# MCU.net
KiCad netlist of a schematic drawn in Altium Designer
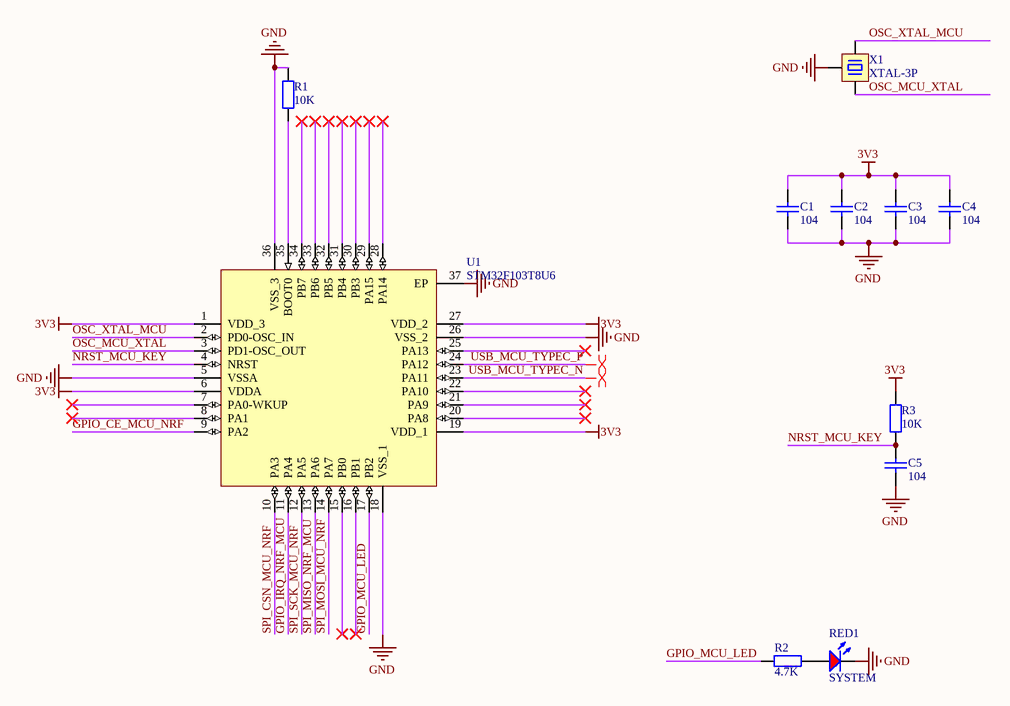
[diagram p0: MCU.SchDoc]

(export (version "E")
  (design (tool "Eeschema 10.0.6"))
  (components
    (comp (ref "C1")
      (value "104")
      (footprint "Cap-0402-M")
      (description "贴片陶瓷电容")
      (libsource (lib "Miscellaneous Base") (part "CAP"))
    )
    (comp (ref "C2")
      (value "104")
      (footprint "Cap-0402-M")
      (description "贴片陶瓷电容")
      (libsource (lib "Miscellaneous Base") (part "CAP"))
    )
    (comp (ref "C3")
      (value "104")
      (footprint "Cap-0402-M")
      (description "贴片陶瓷电容")
      (libsource (lib "Miscellaneous Base") (part "CAP"))
    )
    (comp (ref "C4")
      (value "104")
      (footprint "Cap-0402-M")
      (description "贴片陶瓷电容")
      (libsource (lib "Miscellaneous Base") (part "CAP"))
    )
    (comp (ref "C5")
      (value "104")
      (footprint "Cap-0402-M")
      (description "贴片陶瓷电容")
      (libsource (lib "Miscellaneous Base") (part "CAP"))
    )
    (comp (ref "R1")
      (value "10K")
      (footprint "Res-0402-M")
      (description "贴片电阻")
      (libsource (lib "Miscellaneous Base") (part "RES"))
    )
    (comp (ref "R2")
      (value "4.7K")
      (footprint "Res-0402-M")
      (description "贴片电阻")
      (libsource (lib "") (part "RES_1"))
    )
    (comp (ref "R3")
      (value "10K")
      (footprint "Res-0402-M")
      (description "贴片电阻")
      (libsource (lib "Miscellaneous Base") (part "RES"))
    )
    (comp (ref "RED1")
      (value "SYSTEM")
      (footprint "LED_0603_R")
      (description "发光二极管")
      (libsource (lib "Miscellaneous Transistor") (part "LED_SMD_RED"))
    )
    (comp (ref "U1")
      (value "STM32F103T8U6")
      (footprint "STM-VFQFPN36_L _2")
      (libsource (lib "Miscellaneous MCU") (part "STM32F103T8U6"))
    )
    (comp (ref "X1")
      (value "XTAL-3P")
      (footprint "OSC 3213-3P")
      (description "3脚无源晶振带电容")
      (libsource (lib "Miscellaneous XTAL") (part "XTAL-3P"))
    )
  )
  (nets
    (net (code "1") (name "/GPIO_CE_MCU_NRF") (class "Default")
      (node (ref "U1") (pin "9") (pinfunction "PA2_9") (pintype "bidirectional"))
    )
    (net (code "2") (name "/GPIO_IRQ_NRF_MCU") (class "Default")
      (node (ref "U1") (pin "11") (pinfunction "PA4_11") (pintype "bidirectional"))
    )
    (net (code "3") (name "/GPIO_MCU_LED") (class "Default")
      (node (ref "R2") (pin "2") (pinfunction "2_2") (pintype "passive"))
      (node (ref "U1") (pin "17") (pinfunction "PB2_17") (pintype "bidirectional"))
    )
    (net (code "4") (name "/NRST_MCU_KEY") (class "Default")
      (node (ref "C5") (pin "2") (pinfunction "2_2") (pintype "passive"))
      (node (ref "R3") (pin "1") (pinfunction "1_1") (pintype "passive"))
      (node (ref "U1") (pin "4") (pinfunction "NRST_4") (pintype "bidirectional"))
    )
    (net (code "5") (name "/OSC_MCU_XTAL") (class "Default")
      (node (ref "U1") (pin "3") (pinfunction "PD1-OSC_OUT_3") (pintype "bidirectional"))
      (node (ref "X1") (pin "3") (pinfunction "3_3") (pintype "passive"))
    )
    (net (code "6") (name "/OSC_XTAL_MCU") (class "Default")
      (node (ref "U1") (pin "2") (pinfunction "PD0-OSC_IN_2") (pintype "bidirectional"))
      (node (ref "X1") (pin "1") (pinfunction "1_1") (pintype "passive"))
    )
    (net (code "7") (name "/SPI_CSN_MCU_NRF") (class "Default")
      (node (ref "U1") (pin "10") (pinfunction "PA3_10") (pintype "bidirectional"))
    )
    (net (code "8") (name "/SPI_MISO_NRF_MCU") (class "Default")
      (node (ref "U1") (pin "13") (pinfunction "PA6_13") (pintype "bidirectional"))
    )
    (net (code "9") (name "/SPI_MOSI_MCU_NRF") (class "Default")
      (node (ref "U1") (pin "14") (pinfunction "PA7_14") (pintype "bidirectional"))
    )
    (net (code "10") (name "/SPI_SCK_MCU_NRF") (class "Default")
      (node (ref "U1") (pin "12") (pinfunction "PA5_12") (pintype "bidirectional"))
    )
    (net (code "11") (name "/USB_MCU_TYPEC_N") (class "Default")
      (node (ref "U1") (pin "23") (pinfunction "PA11_23") (pintype "bidirectional"))
    )
    (net (code "12") (name "/USB_MCU_TYPEC_P") (class "Default")
      (node (ref "U1") (pin "24") (pinfunction "PA12_24") (pintype "bidirectional"))
    )
    (net (code "13") (name "3V3") (class "Default")
      (node (ref "C1") (pin "2") (pinfunction "2_2") (pintype "passive"))
      (node (ref "C2") (pin "2") (pinfunction "2_2") (pintype "passive"))
      (node (ref "C3") (pin "2") (pinfunction "2_2") (pintype "passive"))
      (node (ref "C4") (pin "2") (pinfunction "2_2") (pintype "passive"))
      (node (ref "R3") (pin "2") (pinfunction "2_2") (pintype "passive"))
      (node (ref "U1") (pin "1") (pinfunction "VDD_3_1") (pintype "power_in"))
      (node (ref "U1") (pin "19") (pinfunction "VDD_1_19") (pintype "power_in"))
      (node (ref "U1") (pin "27") (pinfunction "VDD_2_27") (pintype "power_in"))
      (node (ref "U1") (pin "6") (pinfunction "VDDA_6") (pintype "power_in"))
    )
    (net (code "14") (name "GND") (class "Default")
      (node (ref "C1") (pin "1") (pinfunction "1_1") (pintype "passive"))
      (node (ref "C2") (pin "1") (pinfunction "1_1") (pintype "passive"))
      (node (ref "C3") (pin "1") (pinfunction "1_1") (pintype "passive"))
      (node (ref "C4") (pin "1") (pinfunction "1_1") (pintype "passive"))
      (node (ref "C5") (pin "1") (pinfunction "1_1") (pintype "passive"))
      (node (ref "R1") (pin "2") (pinfunction "2_2") (pintype "passive"))
      (node (ref "RED1") (pin "2") (pinfunction "K_2") (pintype "passive"))
      (node (ref "U1") (pin "18") (pinfunction "VSS_1_18") (pintype "power_in"))
      (node (ref "U1") (pin "26") (pinfunction "VSS_2_26") (pintype "power_in"))
      (node (ref "U1") (pin "36") (pinfunction "VSS_3_36") (pintype "power_in"))
      (node (ref "U1") (pin "37") (pinfunction "EP_37") (pintype "power_in"))
      (node (ref "U1") (pin "5") (pinfunction "VSSA_5") (pintype "power_in"))
      (node (ref "X1") (pin "2") (pinfunction "2_2") (pintype "passive"))
    )
    (net (code "15") (name "Net-(RED1-A)") (class "Default")
      (node (ref "R2") (pin "1") (pinfunction "1_1") (pintype "passive"))
      (node (ref "RED1") (pin "1") (pinfunction "A_1") (pintype "passive"))
    )
    (net (code "16") (name "Net-(U1-BOOT0)") (class "Default")
      (node (ref "R1") (pin "1") (pinfunction "1_1") (pintype "passive"))
      (node (ref "U1") (pin "35") (pinfunction "BOOT0_35") (pintype "input"))
    )
    (net (code "17") (name "unconnected-(U1-PA0-WKUP-Pad7)") (class "Default")
      (node (ref "U1") (pin "7") (pinfunction "PA0-WKUP_7") (pintype "bidirectional+no_connect"))
    )
    (net (code "18") (name "unconnected-(U1-PA1-Pad8)") (class "Default")
      (node (ref "U1") (pin "8") (pinfunction "PA1_8") (pintype "bidirectional+no_connect"))
    )
    (net (code "19") (name "unconnected-(U1-PA8-Pad20)") (class "Default")
      (node (ref "U1") (pin "20") (pinfunction "PA8_20") (pintype "bidirectional+no_connect"))
    )
    (net (code "20") (name "unconnected-(U1-PA9-Pad21)") (class "Default")
      (node (ref "U1") (pin "21") (pinfunction "PA9_21") (pintype "bidirectional+no_connect"))
    )
    (net (code "21") (name "unconnected-(U1-PA10-Pad22)") (class "Default")
      (node (ref "U1") (pin "22") (pinfunction "PA10_22") (pintype "bidirectional+no_connect"))
    )
    (net (code "22") (name "unconnected-(U1-PA13-Pad25)") (class "Default")
      (node (ref "U1") (pin "25") (pinfunction "PA13_25") (pintype "bidirectional+no_connect"))
    )
    (net (code "23") (name "unconnected-(U1-PA14-Pad28)") (class "Default")
      (node (ref "U1") (pin "28") (pinfunction "PA14_28") (pintype "bidirectional+no_connect"))
    )
    (net (code "24") (name "unconnected-(U1-PA15-Pad29)") (class "Default")
      (node (ref "U1") (pin "29") (pinfunction "PA15_29") (pintype "bidirectional+no_connect"))
    )
    (net (code "25") (name "unconnected-(U1-PB0-Pad15)") (class "Default")
      (node (ref "U1") (pin "15") (pinfunction "PB0_15") (pintype "bidirectional+no_connect"))
    )
    (net (code "26") (name "unconnected-(U1-PB1-Pad16)") (class "Default")
      (node (ref "U1") (pin "16") (pinfunction "PB1_16") (pintype "bidirectional+no_connect"))
    )
    (net (code "27") (name "unconnected-(U1-PB3-Pad30)") (class "Default")
      (node (ref "U1") (pin "30") (pinfunction "PB3_30") (pintype "bidirectional+no_connect"))
    )
    (net (code "28") (name "unconnected-(U1-PB4-Pad31)") (class "Default")
      (node (ref "U1") (pin "31") (pinfunction "PB4_31") (pintype "bidirectional+no_connect"))
    )
    (net (code "29") (name "unconnected-(U1-PB5-Pad32)") (class "Default")
      (node (ref "U1") (pin "32") (pinfunction "PB5_32") (pintype "bidirectional+no_connect"))
    )
    (net (code "30") (name "unconnected-(U1-PB6-Pad33)") (class "Default")
      (node (ref "U1") (pin "33") (pinfunction "PB6_33") (pintype "bidirectional+no_connect"))
    )
    (net (code "31") (name "unconnected-(U1-PB7-Pad34)") (class "Default")
      (node (ref "U1") (pin "34") (pinfunction "PB7_34") (pintype "bidirectional+no_connect"))
    )
  )
)
